# MagusExpander.net
KiCad netlist of a schematic drawn in EAGLE
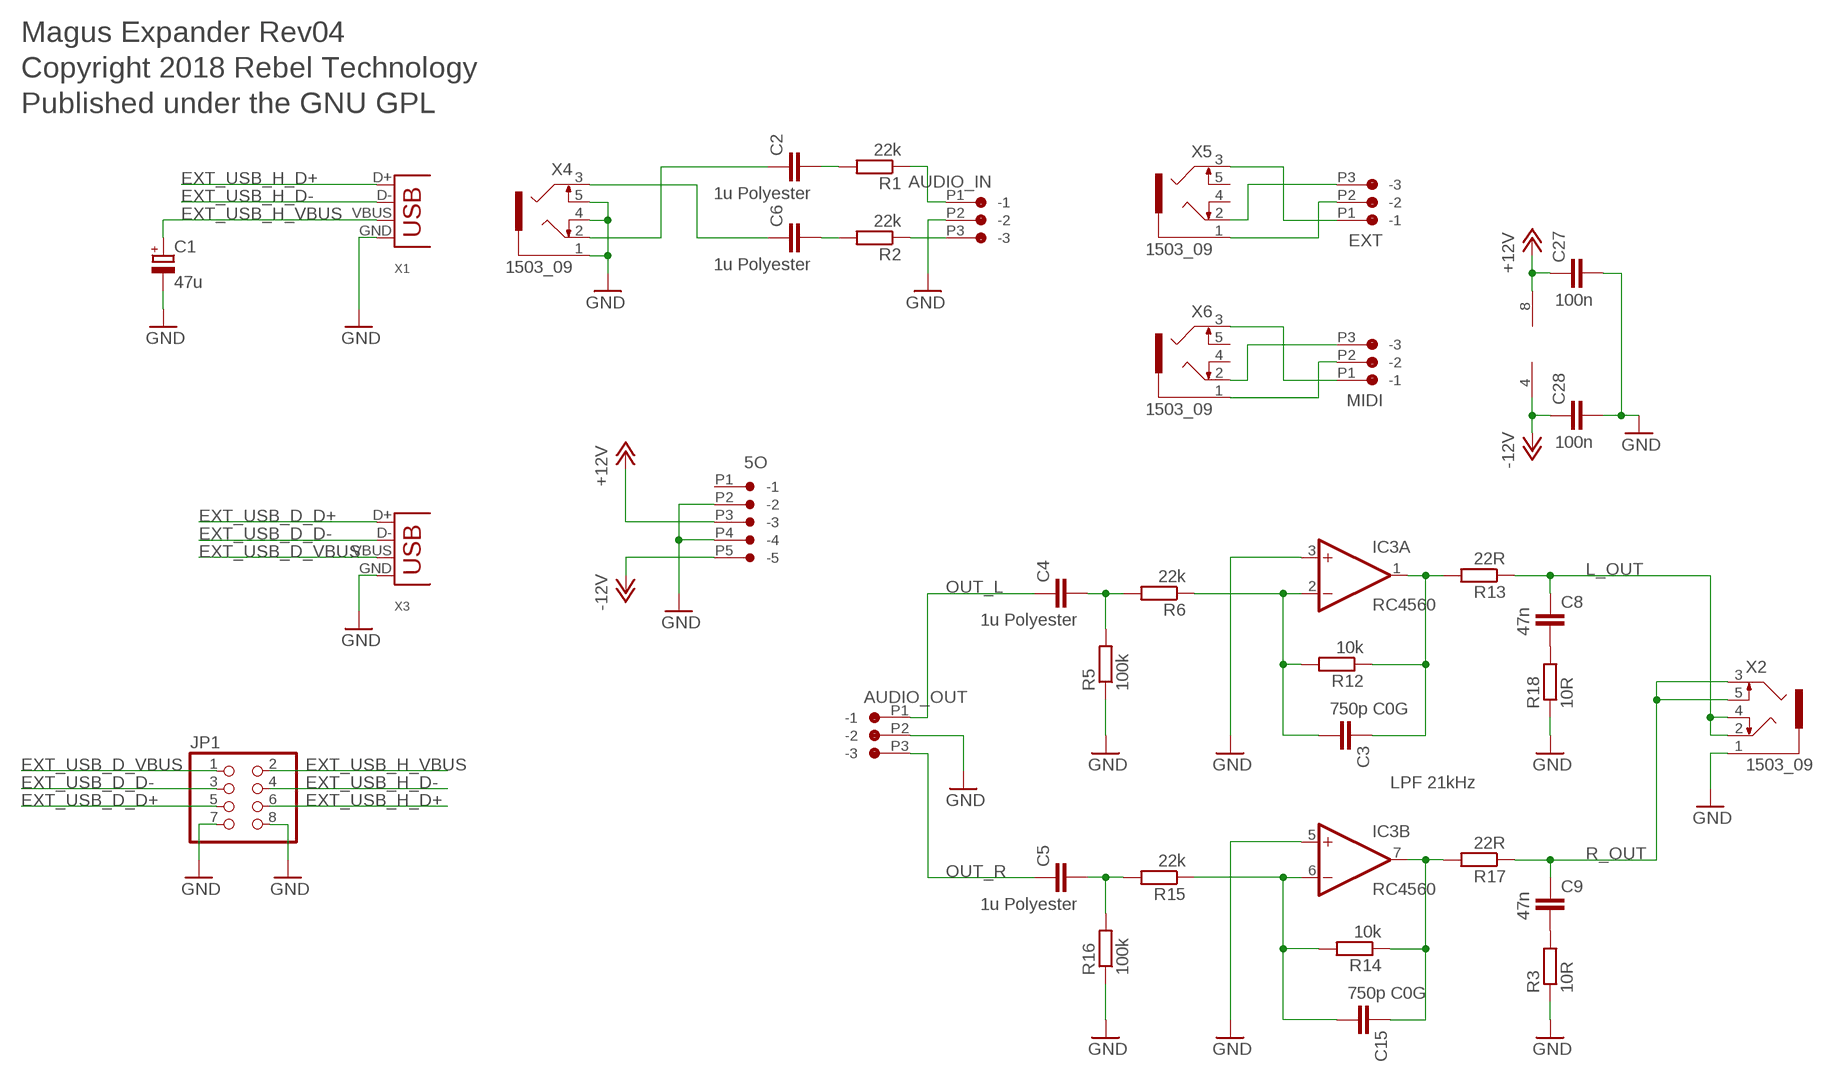
[diagram p0: schematic, sheet 1]

(export (version "E")
  (design (tool "Eeschema 10.0.6"))
  (components
    (comp (ref "5O")
      (value "CON-JST_PH_5W")
      (footprint "eagle-import:CON-JST_PH_5W")
      (libsource (lib "eagle-import") (part "CON-JST_PH_5W"))
    )
    (comp (ref "AUDIO_IN")
      (value "CON-JST_PH_3W")
      (footprint "eagle-import:CON-JST_PH_3W")
      (libsource (lib "eagle-import") (part "CON-JST_PH_3W"))
    )
    (comp (ref "AUDIO_OUT")
      (value "CON-JST_PH_3W")
      (footprint "eagle-import:CON-JST_PH_3W")
      (libsource (lib "eagle-import") (part "CON-JST_PH_3W"))
    )
    (comp (ref "C1")
      (value "47u")
      (footprint "eagle-import:CPOL-5")
      (libsource (lib "eagle-import") (part "CPOL-EU153CLV-0505"))
    )
    (comp (ref "C2")
      (value "1u Polyester")
      (footprint "eagle-import:C1210")
      (libsource (lib "eagle-import") (part "C-EUC1210"))
    )
    (comp (ref "C3")
      (value "750p C0G")
      (footprint "eagle-import:C0603")
      (libsource (lib "eagle-import") (part "C-EUC0603"))
    )
    (comp (ref "C4")
      (value "1u Polyester")
      (footprint "eagle-import:C1210")
      (libsource (lib "eagle-import") (part "C-EUC1210"))
    )
    (comp (ref "C5")
      (value "1u Polyester")
      (footprint "eagle-import:C1210")
      (libsource (lib "eagle-import") (part "C-EUC1210"))
    )
    (comp (ref "C6")
      (value "1u Polyester")
      (footprint "eagle-import:C1210")
      (libsource (lib "eagle-import") (part "C-EUC1210"))
    )
    (comp (ref "C8")
      (value "47n")
      (footprint "eagle-import:C0603")
      (libsource (lib "eagle-import") (part "C-EUC0603"))
    )
    (comp (ref "C9")
      (value "47n")
      (footprint "eagle-import:C0603")
      (libsource (lib "eagle-import") (part "C-EUC0603"))
    )
    (comp (ref "C15")
      (value "750p C0G")
      (footprint "eagle-import:C0603")
      (libsource (lib "eagle-import") (part "C-EUC0603"))
    )
    (comp (ref "C27")
      (value "100n")
      (footprint "eagle-import:C0603")
      (libsource (lib "eagle-import") (part "C-EUC0603"))
    )
    (comp (ref "C28")
      (value "100n")
      (footprint "eagle-import:C0603")
      (libsource (lib "eagle-import") (part "C-EUC0603"))
    )
    (comp (ref "EXT")
      (value "CON-JST_PH_3W")
      (footprint "eagle-import:CON-JST_PH_3W")
      (libsource (lib "eagle-import") (part "CON-JST_PH_3W"))
    )
    (comp (ref "IC3")
      (value "RC4560")
      (footprint "eagle-import:SO08")
      (libsource (lib "eagle-import") (part "NE5532D"))
    )
    (comp (ref "JP1")
      (value "PINHD-2X4")
      (footprint "eagle-import:2X04")
      (libsource (lib "eagle-import") (part "PINHD-2X4"))
    )
    (comp (ref "MIDI")
      (value "CON-JST_PH_3W")
      (footprint "eagle-import:CON-JST_PH_3W")
      (libsource (lib "eagle-import") (part "CON-JST_PH_3W"))
    )
    (comp (ref "R1")
      (value "22k")
      (footprint "eagle-import:R0603")
      (libsource (lib "eagle-import") (part "R-EU_R0603"))
    )
    (comp (ref "R2")
      (value "22k")
      (footprint "eagle-import:R0603")
      (libsource (lib "eagle-import") (part "R-EU_R0603"))
    )
    (comp (ref "R3")
      (value "10R")
      (footprint "eagle-import:R0603")
      (libsource (lib "eagle-import") (part "R-EU_R0603"))
    )
    (comp (ref "R5")
      (value "100k")
      (footprint "eagle-import:R0603")
      (libsource (lib "eagle-import") (part "R-EU_R0603"))
    )
    (comp (ref "R6")
      (value "22k")
      (footprint "eagle-import:R0603")
      (libsource (lib "eagle-import") (part "R-EU_R0603"))
    )
    (comp (ref "R12")
      (value "10k")
      (footprint "eagle-import:R0603")
      (libsource (lib "eagle-import") (part "R-EU_R0603"))
    )
    (comp (ref "R13")
      (value "22R")
      (footprint "eagle-import:R0603")
      (libsource (lib "eagle-import") (part "R-EU_R0603"))
    )
    (comp (ref "R14")
      (value "10k")
      (footprint "eagle-import:R0603")
      (libsource (lib "eagle-import") (part "R-EU_R0603"))
    )
    (comp (ref "R15")
      (value "22k")
      (footprint "eagle-import:R0603")
      (libsource (lib "eagle-import") (part "R-EU_R0603"))
    )
    (comp (ref "R16")
      (value "100k")
      (footprint "eagle-import:R0603")
      (libsource (lib "eagle-import") (part "R-EU_R0603"))
    )
    (comp (ref "R17")
      (value "22R")
      (footprint "eagle-import:R0603")
      (libsource (lib "eagle-import") (part "R-EU_R0603"))
    )
    (comp (ref "R18")
      (value "10R")
      (footprint "eagle-import:R0603")
      (libsource (lib "eagle-import") (part "R-EU_R0603"))
    )
    (comp (ref "X1")
      (value "USB-A-H")
      (footprint "eagle-import:USB-A-H")
      (libsource (lib "eagle-import") (part "USB-A-H"))
    )
    (comp (ref "X2")
      (value "1503_09")
      (footprint "eagle-import:1503_09")
      (libsource (lib "eagle-import") (part "1503_09"))
    )
    (comp (ref "X3")
      (value "USB-B-H")
      (footprint "eagle-import:USB-B-H")
      (libsource (lib "eagle-import") (part "USB-B-H"))
    )
    (comp (ref "X4")
      (value "1503_09")
      (footprint "eagle-import:1503_09")
      (libsource (lib "eagle-import") (part "1503_09"))
    )
    (comp (ref "X5")
      (value "1503_09")
      (footprint "eagle-import:1503_09")
      (libsource (lib "eagle-import") (part "1503_09"))
    )
    (comp (ref "X6")
      (value "1503_09")
      (footprint "eagle-import:1503_09")
      (libsource (lib "eagle-import") (part "1503_09"))
    )
  )
  (nets
    (net (code "1") (name "+12V") (class "Default")
      (node (ref "5O") (pin "P3") (pinfunction "-3_P3") (pintype "bidirectional"))
      (node (ref "C27") (pin "1") (pinfunction "1_1") (pintype "passive"))
      (node (ref "IC3") (pin "8") (pinfunction "V+_8") (pintype "power_in"))
    )
    (net (code "2") (name "-12V") (class "Default")
      (node (ref "5O") (pin "P5") (pinfunction "-5_P5") (pintype "bidirectional"))
      (node (ref "C28") (pin "1") (pinfunction "1_1") (pintype "passive"))
      (node (ref "IC3") (pin "4") (pinfunction "V-_4") (pintype "power_in"))
    )
    (net (code "3") (name "/EXT_USB_D_D+") (class "Default")
      (node (ref "JP1") (pin "5") (pinfunction "5_5") (pintype "passive"))
      (node (ref "X3") (pin "D+") (pinfunction "D+_D+") (pintype "bidirectional"))
    )
    (net (code "4") (name "/EXT_USB_D_D-") (class "Default")
      (node (ref "JP1") (pin "3") (pinfunction "3_3") (pintype "passive"))
      (node (ref "X3") (pin "D-") (pinfunction "D-_D-") (pintype "bidirectional"))
    )
    (net (code "5") (name "/EXT_USB_D_VBUS") (class "Default")
      (node (ref "JP1") (pin "1") (pinfunction "1_1") (pintype "passive"))
      (node (ref "X3") (pin "VBUS") (pinfunction "VBUS_VBUS") (pintype "bidirectional"))
    )
    (net (code "6") (name "/EXT_USB_H_D+") (class "Default")
      (node (ref "JP1") (pin "6") (pinfunction "6_6") (pintype "passive"))
      (node (ref "X1") (pin "D+") (pinfunction "D+_D+") (pintype "bidirectional"))
    )
    (net (code "7") (name "/EXT_USB_H_D-") (class "Default")
      (node (ref "JP1") (pin "4") (pinfunction "4_4") (pintype "passive"))
      (node (ref "X1") (pin "D-") (pinfunction "D-_D-") (pintype "bidirectional"))
    )
    (net (code "8") (name "/EXT_USB_H_VBUS") (class "Default")
      (node (ref "C1") (pin "+") (pinfunction "+_+") (pintype "passive"))
      (node (ref "JP1") (pin "2") (pinfunction "2_2") (pintype "passive"))
      (node (ref "X1") (pin "VBUS") (pinfunction "VBUS_VBUS") (pintype "bidirectional"))
    )
    (net (code "9") (name "/L_OUT") (class "Default")
      (node (ref "C8") (pin "1") (pinfunction "1_1") (pintype "passive"))
      (node (ref "R13") (pin "1") (pinfunction "1_1") (pintype "passive"))
      (node (ref "X2") (pin "2") (pinfunction "2_2") (pintype "passive"))
      (node (ref "X2") (pin "4") (pinfunction "4_4") (pintype "passive"))
    )
    (net (code "10") (name "/OUT_L") (class "Default")
      (node (ref "AUDIO_OUT") (pin "P1") (pinfunction "-1_P1") (pintype "bidirectional"))
      (node (ref "C4") (pin "1") (pinfunction "1_1") (pintype "passive"))
    )
    (net (code "11") (name "/OUT_R") (class "Default")
      (node (ref "AUDIO_OUT") (pin "P3") (pinfunction "-3_P3") (pintype "bidirectional"))
      (node (ref "C5") (pin "1") (pinfunction "1_1") (pintype "passive"))
    )
    (net (code "12") (name "/R_OUT") (class "Default")
      (node (ref "C9") (pin "1") (pinfunction "1_1") (pintype "passive"))
      (node (ref "R17") (pin "1") (pinfunction "1_1") (pintype "passive"))
      (node (ref "X2") (pin "3") (pinfunction "3_3") (pintype "passive"))
      (node (ref "X2") (pin "5") (pinfunction "5_5") (pintype "passive"))
    )
    (net (code "13") (name "GND") (class "Default")
      (node (ref "5O") (pin "P2") (pinfunction "-2_P2") (pintype "bidirectional"))
      (node (ref "5O") (pin "P4") (pinfunction "-4_P4") (pintype "bidirectional"))
      (node (ref "AUDIO_IN") (pin "P2") (pinfunction "-2_P2") (pintype "bidirectional"))
      (node (ref "AUDIO_OUT") (pin "P2") (pinfunction "-2_P2") (pintype "bidirectional"))
      (node (ref "C1") (pin "-") (pinfunction "-_-") (pintype "passive"))
      (node (ref "C27") (pin "2") (pinfunction "2_2") (pintype "passive"))
      (node (ref "C28") (pin "2") (pinfunction "2_2") (pintype "passive"))
      (node (ref "IC3") (pin "3") (pinfunction "+IN_3") (pintype "input"))
      (node (ref "IC3") (pin "5") (pinfunction "+IN_5") (pintype "input"))
      (node (ref "JP1") (pin "7") (pinfunction "7_7") (pintype "passive"))
      (node (ref "JP1") (pin "8") (pinfunction "8_8") (pintype "passive"))
      (node (ref "R16") (pin "1") (pinfunction "1_1") (pintype "passive"))
      (node (ref "R18") (pin "1") (pinfunction "1_1") (pintype "passive"))
      (node (ref "R3") (pin "1") (pinfunction "1_1") (pintype "passive"))
      (node (ref "R5") (pin "1") (pinfunction "1_1") (pintype "passive"))
      (node (ref "X1") (pin "GND") (pinfunction "GND_GND") (pintype "bidirectional"))
      (node (ref "X2") (pin "1") (pinfunction "1_1") (pintype "passive"))
      (node (ref "X3") (pin "GND") (pinfunction "GND_GND") (pintype "bidirectional"))
      (node (ref "X4") (pin "1") (pinfunction "1_1") (pintype "passive"))
      (node (ref "X4") (pin "4") (pinfunction "4_4") (pintype "passive"))
      (node (ref "X4") (pin "5") (pinfunction "5_5") (pintype "passive"))
    )
    (net (code "14") (name "Net-(AUDIO_IN--1)") (class "Default")
      (node (ref "AUDIO_IN") (pin "P1") (pinfunction "-1_P1") (pintype "bidirectional"))
      (node (ref "R1") (pin "1") (pinfunction "1_1") (pintype "passive"))
    )
    (net (code "15") (name "Net-(AUDIO_IN--3)") (class "Default")
      (node (ref "AUDIO_IN") (pin "P3") (pinfunction "-3_P3") (pintype "bidirectional"))
      (node (ref "R2") (pin "1") (pinfunction "1_1") (pintype "passive"))
    )
    (net (code "16") (name "Net-(C2-Pad1)") (class "Default")
      (node (ref "C2") (pin "1") (pinfunction "1_1") (pintype "passive"))
      (node (ref "X4") (pin "2") (pinfunction "2_2") (pintype "passive"))
    )
    (net (code "17") (name "Net-(C2-Pad2)") (class "Default")
      (node (ref "C2") (pin "2") (pinfunction "2_2") (pintype "passive"))
      (node (ref "R1") (pin "2") (pinfunction "2_2") (pintype "passive"))
    )
    (net (code "18") (name "Net-(C4-Pad2)") (class "Default")
      (node (ref "C4") (pin "2") (pinfunction "2_2") (pintype "passive"))
      (node (ref "R5") (pin "2") (pinfunction "2_2") (pintype "passive"))
      (node (ref "R6") (pin "2") (pinfunction "2_2") (pintype "passive"))
    )
    (net (code "19") (name "Net-(C5-Pad2)") (class "Default")
      (node (ref "C5") (pin "2") (pinfunction "2_2") (pintype "passive"))
      (node (ref "R15") (pin "2") (pinfunction "2_2") (pintype "passive"))
      (node (ref "R16") (pin "2") (pinfunction "2_2") (pintype "passive"))
    )
    (net (code "20") (name "Net-(C6-Pad1)") (class "Default")
      (node (ref "C6") (pin "1") (pinfunction "1_1") (pintype "passive"))
      (node (ref "X4") (pin "3") (pinfunction "3_3") (pintype "passive"))
    )
    (net (code "21") (name "Net-(C6-Pad2)") (class "Default")
      (node (ref "C6") (pin "2") (pinfunction "2_2") (pintype "passive"))
      (node (ref "R2") (pin "2") (pinfunction "2_2") (pintype "passive"))
    )
    (net (code "22") (name "Net-(C8-Pad2)") (class "Default")
      (node (ref "C8") (pin "2") (pinfunction "2_2") (pintype "passive"))
      (node (ref "R18") (pin "2") (pinfunction "2_2") (pintype "passive"))
    )
    (net (code "23") (name "Net-(C9-Pad2)") (class "Default")
      (node (ref "C9") (pin "2") (pinfunction "2_2") (pintype "passive"))
      (node (ref "R3") (pin "2") (pinfunction "2_2") (pintype "passive"))
    )
    (net (code "24") (name "Net-(EXT--1)") (class "Default")
      (node (ref "EXT") (pin "P1") (pinfunction "-1_P1") (pintype "bidirectional"))
      (node (ref "X5") (pin "3") (pinfunction "3_3") (pintype "passive"))
    )
    (net (code "25") (name "Net-(EXT--2)") (class "Default")
      (node (ref "EXT") (pin "P2") (pinfunction "-2_P2") (pintype "bidirectional"))
      (node (ref "X5") (pin "1") (pinfunction "1_1") (pintype "passive"))
    )
    (net (code "26") (name "Net-(EXT--3)") (class "Default")
      (node (ref "EXT") (pin "P3") (pinfunction "-3_P3") (pintype "bidirectional"))
      (node (ref "X5") (pin "2") (pinfunction "2_2") (pintype "passive"))
    )
    (net (code "27") (name "Net-(IC3A--IN)") (class "Default")
      (node (ref "C3") (pin "2") (pinfunction "2_2") (pintype "passive"))
      (node (ref "IC3") (pin "2") (pinfunction "-IN_2") (pintype "input"))
      (node (ref "R12") (pin "2") (pinfunction "2_2") (pintype "passive"))
      (node (ref "R6") (pin "1") (pinfunction "1_1") (pintype "passive"))
    )
    (net (code "28") (name "Net-(IC3A-OUT)") (class "Default")
      (node (ref "C3") (pin "1") (pinfunction "1_1") (pintype "passive"))
      (node (ref "IC3") (pin "1") (pinfunction "OUT_1") (pintype "output"))
      (node (ref "R12") (pin "1") (pinfunction "1_1") (pintype "passive"))
      (node (ref "R13") (pin "2") (pinfunction "2_2") (pintype "passive"))
    )
    (net (code "29") (name "Net-(IC3B--IN)") (class "Default")
      (node (ref "C15") (pin "2") (pinfunction "2_2") (pintype "passive"))
      (node (ref "IC3") (pin "6") (pinfunction "-IN_6") (pintype "input"))
      (node (ref "R14") (pin "2") (pinfunction "2_2") (pintype "passive"))
      (node (ref "R15") (pin "1") (pinfunction "1_1") (pintype "passive"))
    )
    (net (code "30") (name "Net-(IC3B-OUT)") (class "Default")
      (node (ref "C15") (pin "1") (pinfunction "1_1") (pintype "passive"))
      (node (ref "IC3") (pin "7") (pinfunction "OUT_7") (pintype "output"))
      (node (ref "R14") (pin "1") (pinfunction "1_1") (pintype "passive"))
      (node (ref "R17") (pin "2") (pinfunction "2_2") (pintype "passive"))
    )
    (net (code "31") (name "Net-(MIDI--1)") (class "Default")
      (node (ref "MIDI") (pin "P1") (pinfunction "-1_P1") (pintype "bidirectional"))
      (node (ref "X6") (pin "3") (pinfunction "3_3") (pintype "passive"))
    )
    (net (code "32") (name "Net-(MIDI--2)") (class "Default")
      (node (ref "MIDI") (pin "P2") (pinfunction "-2_P2") (pintype "bidirectional"))
      (node (ref "X6") (pin "1") (pinfunction "1_1") (pintype "passive"))
    )
    (net (code "33") (name "Net-(MIDI--3)") (class "Default")
      (node (ref "MIDI") (pin "P3") (pinfunction "-3_P3") (pintype "bidirectional"))
      (node (ref "X6") (pin "2") (pinfunction "2_2") (pintype "passive"))
    )
    (net (code "34") (name "unconnected-(5O--1-PadP1)") (class "Default")
      (node (ref "5O") (pin "P1") (pinfunction "-1_P1") (pintype "bidirectional"))
    )
    (net (code "35") (name "unconnected-(X5-Pad4)") (class "Default")
      (node (ref "X5") (pin "4") (pinfunction "4_4") (pintype "passive"))
    )
    (net (code "36") (name "unconnected-(X5-Pad5)") (class "Default")
      (node (ref "X5") (pin "5") (pinfunction "5_5") (pintype "passive"))
    )
    (net (code "37") (name "unconnected-(X6-Pad4)") (class "Default")
      (node (ref "X6") (pin "4") (pinfunction "4_4") (pintype "passive"))
    )
    (net (code "38") (name "unconnected-(X6-Pad5)") (class "Default")
      (node (ref "X6") (pin "5") (pinfunction "5_5") (pintype "passive"))
    )
  )
)
